# Gimbal-Mastboard.net
KiCad netlist of a schematic drawn in EAGLE
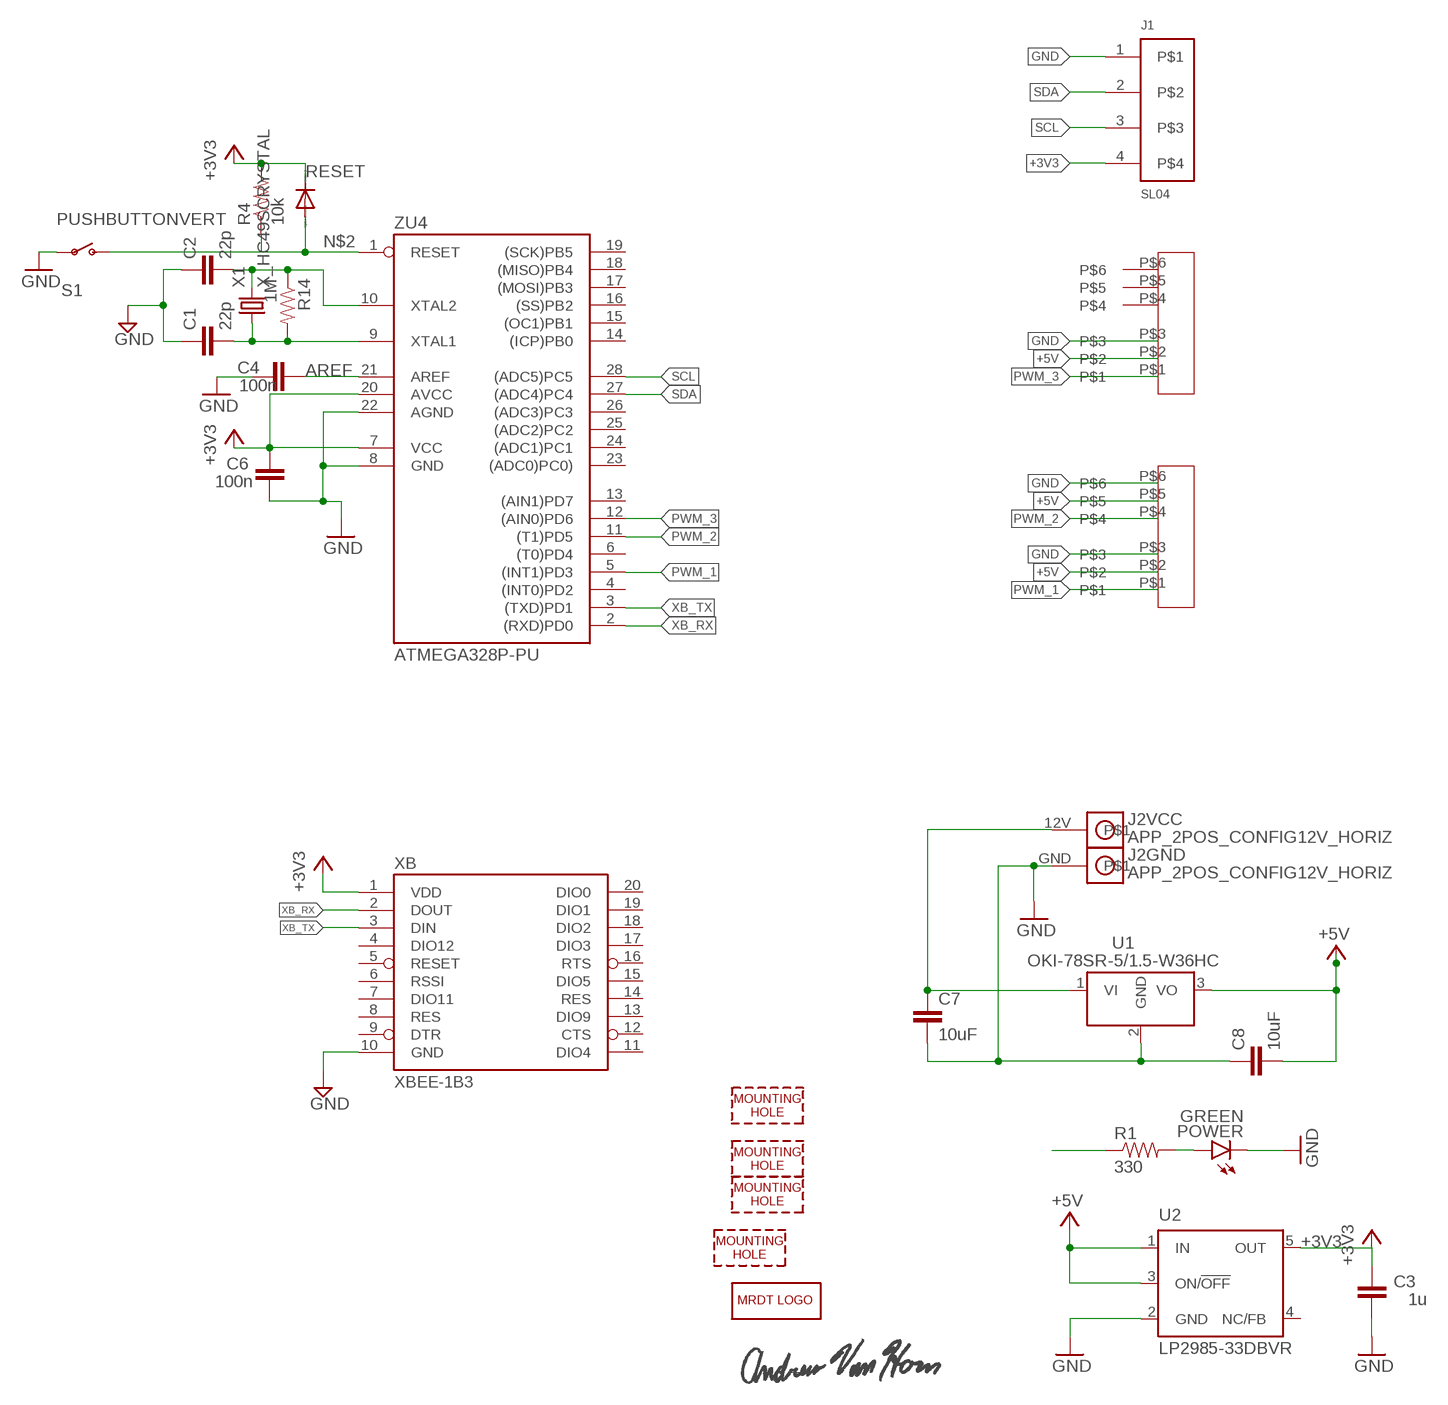
[diagram p0: schematic, sheet 1]

(export (version "E")
  (design (tool "Eeschema 10.0.6"))
  (components
    (comp (ref "C1")
      (value "22p")
      (footprint "eagle-import:0603-CAP")
      (libsource (lib "eagle-import") (part "SparkFun-Passives_CAP0603-CAP"))
    )
    (comp (ref "C2")
      (value "22p")
      (footprint "eagle-import:0603-CAP")
      (libsource (lib "eagle-import") (part "SparkFun-Passives_CAP0603-CAP"))
    )
    (comp (ref "C3")
      (value "1u")
      (footprint "eagle-import:C0603-ROUND")
      (libsource (lib "eagle-import") (part "C-EU0603-RND"))
    )
    (comp (ref "C4")
      (value "100n")
      (footprint "eagle-import:C0603-ROUND")
      (libsource (lib "eagle-import") (part "C-EU0603-RND"))
    )
    (comp (ref "C6")
      (value "100n")
      (footprint "eagle-import:C0603-ROUND")
      (libsource (lib "eagle-import") (part "C-EU0603-RND"))
    )
    (comp (ref "C7")
      (value "10uF")
      (footprint "eagle-import:0805")
      (libsource (lib "eagle-import") (part "CAP0805"))
    )
    (comp (ref "C8")
      (value "10uF")
      (footprint "eagle-import:0805")
      (libsource (lib "eagle-import") (part "CAP0805"))
    )
    (comp (ref "H1")
      (value "MOUNTING_HOLE#4")
      (footprint "eagle-import:#4_SCREW")
      (libsource (lib "eagle-import") (part "MOUNTING_HOLE#4"))
    )
    (comp (ref "H2")
      (value "MOUNTING_HOLE#4")
      (footprint "eagle-import:#4_SCREW")
      (libsource (lib "eagle-import") (part "MOUNTING_HOLE#4"))
    )
    (comp (ref "H3")
      (value "MOUNTING_HOLE#4")
      (footprint "eagle-import:#4_SCREW")
      (libsource (lib "eagle-import") (part "MOUNTING_HOLE#4"))
    )
    (comp (ref "H4")
      (value "MOUNTING_HOLE#4")
      (footprint "eagle-import:#4_SCREW")
      (libsource (lib "eagle-import") (part "MOUNTING_HOLE#4"))
    )
    (comp (ref "J1")
      (value "SL04")
      (footprint "eagle-import:MOLEX_SL_04_TH")
      (libsource (lib "eagle-import") (part "SL04"))
    )
    (comp (ref "J2")
      (value "APP_2POS_CONFIG12V_HORIZ")
      (footprint "eagle-import:APP45_12V_HORIZ_CONFIG")
      (libsource (lib "eagle-import") (part "APP_2POS_CONFIG12V_HORIZ"))
    )
    (comp (ref "LOGO1")
      (value "MRDT_LOGO")
      (footprint "eagle-import:MRDT_LOGO")
      (libsource (lib "eagle-import") (part "MRDT_LOGO"))
    )
    (comp (ref "POWER")
      (value "GREEN")
      (footprint "eagle-import:LED-1206")
      (libsource (lib "eagle-import") (part "LED-GREEN1206"))
    )
    (comp (ref "R1")
      (value "330")
      (footprint "eagle-import:0805")
      (libsource (lib "eagle-import") (part "0.22OHM-1/4W-1%(0805)"))
    )
    (comp (ref "R4")
      (value "10k")
      (footprint "eagle-import:0805")
      (libsource (lib "eagle-import") (part "0.22OHM-1/4W-1%(0805)"))
    )
    (comp (ref "R14")
      (value "1M")
      (footprint "eagle-import:0603-RES")
      (libsource (lib "eagle-import") (part "RESISTOR0603"))
    )
    (comp (ref "RESET")
      (value "CD1206-S01575")
      (footprint "eagle-import:MINIMELF")
      (libsource (lib "eagle-import") (part "DIODE-MINIMELF"))
    )
    (comp (ref "S1")
      (value "PUSHBUTTONVERT")
      (footprint "eagle-import:APEM-MJTP1243")
      (fields (field (name "PARTNO") "MJTP1243"))
      (libsource (lib "eagle-import") (part "PUSHBUTTONVERT"))
    )
    (comp (ref "U$1")
      (value "2X3_BOX_HEADER_FEMALE")
      (footprint "eagle-import:2X3_BOX_HEADER_FEMALE")
      (libsource (lib "eagle-import") (part "2X3_BOX_HEADER_FEMALE"))
    )
    (comp (ref "U$2")
      (value "2X3_BOX_HEADER_FEMALE")
      (footprint "eagle-import:2X3_BOX_HEADER_FEMALE")
      (libsource (lib "eagle-import") (part "2X3_BOX_HEADER_FEMALE"))
    )
    (comp (ref "U$3")
      (value "ANDREW_VAN_HORN_SIGNATURE")
      (footprint "eagle-import:ANDREW_VAN_HORN_SIGNATURE")
      (libsource (lib "eagle-import") (part "ANDREW_VAN_HORN_SIGNATURE"))
    )
    (comp (ref "U1")
      (value "OKI-78SR-5/1.5-W36HC")
      (footprint "eagle-import:OKI-78SR_HORIZ")
      (libsource (lib "eagle-import") (part "OKI-78SR-/1.5-W36?CH5"))
    )
    (comp (ref "U2")
      (value "LP2985-33DBVR")
      (footprint "eagle-import:SOT23-DBV")
      (libsource (lib "eagle-import") (part "LP2985-XXDBVR33"))
    )
    (comp (ref "X1")
      (value "X_HC49SCRYSTAL")
      (footprint "eagle-import:HC-49")
      (libsource (lib "eagle-import") (part "X_HC49SCRYSTAL"))
    )
    (comp (ref "XB")
      (value "XBEE-1B3")
      (footprint "eagle-import:XBEE-SMD")
      (libsource (lib "eagle-import") (part "XBEE-1B3"))
    )
    (comp (ref "ZU4")
      (value "ATMEGA328P-PU")
      (footprint "eagle-import:DIL28-3")
      (libsource (lib "eagle-import") (part "ATMEGA328P-PU"))
    )
  )
  (nets
    (net (code "1") (name "+3V3") (class "Default")
      (node (ref "C3") (pin "2") (pinfunction "2_2") (pintype "passive"))
      (node (ref "C6") (pin "2") (pinfunction "2_2") (pintype "passive"))
      (node (ref "J1") (pin "4") (pinfunction "P$4_4") (pintype "bidirectional"))
      (node (ref "R1") (pin "1") (pinfunction "1_1") (pintype "passive"))
      (node (ref "R4") (pin "2") (pinfunction "2_2") (pintype "passive"))
      (node (ref "RESET") (pin "C") (pinfunction "C_C") (pintype "passive"))
      (node (ref "U2") (pin "5") (pinfunction "OUT_5") (pintype "passive"))
      (node (ref "XB") (pin "1") (pinfunction "VDD_1") (pintype "power_in"))
      (node (ref "ZU4") (pin "20") (pinfunction "AVCC_20") (pintype "power_in"))
      (node (ref "ZU4") (pin "7") (pinfunction "VCC_7") (pintype "power_in"))
    )
    (net (code "2") (name "+5V") (class "Default")
      (node (ref "C8") (pin "2") (pinfunction "2_2") (pintype "passive"))
      (node (ref "U$1") (pin "P$2") (pinfunction "P$2_P$2") (pintype "bidirectional"))
      (node (ref "U$2") (pin "P$2") (pinfunction "P$2_P$2") (pintype "bidirectional"))
      (node (ref "U$2") (pin "P$5") (pinfunction "P$5_P$5") (pintype "bidirectional"))
      (node (ref "U1") (pin "3") (pinfunction "VO_3") (pintype "bidirectional"))
      (node (ref "U2") (pin "1") (pinfunction "IN_1") (pintype "input"))
      (node (ref "U2") (pin "3") (pinfunction "ON/~{OFF}_3") (pintype "input"))
    )
    (net (code "3") (name "/AREF") (class "Default")
      (node (ref "C4") (pin "2") (pinfunction "2_2") (pintype "passive"))
      (node (ref "ZU4") (pin "21") (pinfunction "AREF_21") (pintype "passive"))
    )
    (net (code "4") (name "/N$2") (class "Default")
      (node (ref "R4") (pin "1") (pinfunction "1_1") (pintype "passive"))
      (node (ref "RESET") (pin "A") (pinfunction "A_A") (pintype "passive"))
      (node (ref "S1") (pin "P$2") (pinfunction "S_P$2") (pintype "passive"))
      (node (ref "ZU4") (pin "1") (pinfunction "RESET_1") (pintype "input"))
    )
    (net (code "5") (name "GND") (class "Default")
      (node (ref "C1") (pin "1") (pinfunction "1_1") (pintype "passive"))
      (node (ref "C2") (pin "1") (pinfunction "1_1") (pintype "passive"))
      (node (ref "C3") (pin "1") (pinfunction "1_1") (pintype "passive"))
      (node (ref "C4") (pin "1") (pinfunction "1_1") (pintype "passive"))
      (node (ref "C6") (pin "1") (pinfunction "1_1") (pintype "passive"))
      (node (ref "C7") (pin "2") (pinfunction "2_2") (pintype "passive"))
      (node (ref "C8") (pin "1") (pinfunction "1_1") (pintype "passive"))
      (node (ref "J1") (pin "1") (pinfunction "P$1_1") (pintype "bidirectional"))
      (node (ref "J2") (pin "GND") (pinfunction "P$1_GND") (pintype "bidirectional"))
      (node (ref "POWER") (pin "C") (pinfunction "C_C") (pintype "passive"))
      (node (ref "S1") (pin "P$1") (pinfunction "P_P$1") (pintype "passive"))
      (node (ref "U$1") (pin "P$3") (pinfunction "P$3_P$3") (pintype "bidirectional"))
      (node (ref "U$2") (pin "P$3") (pinfunction "P$3_P$3") (pintype "bidirectional"))
      (node (ref "U$2") (pin "P$6") (pinfunction "P$6_P$6") (pintype "bidirectional"))
      (node (ref "U1") (pin "2") (pinfunction "GND_2") (pintype "bidirectional"))
      (node (ref "U2") (pin "2") (pinfunction "GND_2") (pintype "power_in"))
      (node (ref "XB") (pin "10") (pinfunction "GND_10") (pintype "power_in"))
      (node (ref "ZU4") (pin "22") (pinfunction "AGND_22") (pintype "power_in"))
      (node (ref "ZU4") (pin "8") (pinfunction "GND_8") (pintype "power_in"))
    )
    (net (code "6") (name "Net-(J2B-P$1)") (class "Default")
      (node (ref "C7") (pin "1") (pinfunction "1_1") (pintype "passive"))
      (node (ref "J2") (pin "12V") (pinfunction "P$1_12V") (pintype "bidirectional"))
      (node (ref "U1") (pin "1") (pinfunction "VI_1") (pintype "bidirectional"))
    )
    (net (code "7") (name "Net-(POWER-PadA)") (class "Default")
      (node (ref "POWER") (pin "A") (pinfunction "A_A") (pintype "passive"))
      (node (ref "R1") (pin "2") (pinfunction "2_2") (pintype "passive"))
    )
    (net (code "8") (name "Net-(X1-1)") (class "Default")
      (node (ref "C1") (pin "2") (pinfunction "2_2") (pintype "passive"))
      (node (ref "R14") (pin "2") (pinfunction "2_2") (pintype "passive"))
      (node (ref "X1") (pin "P$1") (pinfunction "1_P$1") (pintype "passive"))
      (node (ref "ZU4") (pin "9") (pinfunction "XTAL1_9") (pintype "bidirectional"))
    )
    (net (code "9") (name "Net-(X1-2)") (class "Default")
      (node (ref "C2") (pin "2") (pinfunction "2_2") (pintype "passive"))
      (node (ref "R14") (pin "1") (pinfunction "1_1") (pintype "passive"))
      (node (ref "X1") (pin "P$2") (pinfunction "2_P$2") (pintype "passive"))
      (node (ref "ZU4") (pin "10") (pinfunction "XTAL2_10") (pintype "bidirectional"))
    )
    (net (code "10") (name "PWM_1") (class "Default")
      (node (ref "U$2") (pin "P$1") (pinfunction "P$1_P$1") (pintype "bidirectional"))
      (node (ref "ZU4") (pin "5") (pinfunction "(INT1)PD3_5") (pintype "bidirectional"))
    )
    (net (code "11") (name "PWM_2") (class "Default")
      (node (ref "U$2") (pin "P$4") (pinfunction "P$4_P$4") (pintype "bidirectional"))
      (node (ref "ZU4") (pin "11") (pinfunction "(T1)PD5_11") (pintype "bidirectional"))
    )
    (net (code "12") (name "PWM_3") (class "Default")
      (node (ref "U$1") (pin "P$1") (pinfunction "P$1_P$1") (pintype "bidirectional"))
      (node (ref "ZU4") (pin "12") (pinfunction "(AIN0)PD6_12") (pintype "bidirectional"))
    )
    (net (code "13") (name "SCL") (class "Default")
      (node (ref "J1") (pin "3") (pinfunction "P$3_3") (pintype "bidirectional"))
      (node (ref "ZU4") (pin "28") (pinfunction "(ADC5)PC5_28") (pintype "bidirectional"))
    )
    (net (code "14") (name "SDA") (class "Default")
      (node (ref "J1") (pin "2") (pinfunction "P$2_2") (pintype "bidirectional"))
      (node (ref "ZU4") (pin "27") (pinfunction "(ADC4)PC4_27") (pintype "bidirectional"))
    )
    (net (code "15") (name "XB_RX") (class "Default")
      (node (ref "XB") (pin "2") (pinfunction "DOUT_2") (pintype "output"))
      (node (ref "ZU4") (pin "2") (pinfunction "(RXD)PD0_2") (pintype "bidirectional"))
    )
    (net (code "16") (name "XB_TX") (class "Default")
      (node (ref "XB") (pin "3") (pinfunction "DIN_3") (pintype "input"))
      (node (ref "ZU4") (pin "3") (pinfunction "(TXD)PD1_3") (pintype "bidirectional"))
    )
    (net (code "17") (name "unconnected-(U$1-PadP$4)") (class "Default")
      (node (ref "U$1") (pin "P$4") (pinfunction "P$4_P$4") (pintype "bidirectional"))
    )
    (net (code "18") (name "unconnected-(U$1-PadP$5)") (class "Default")
      (node (ref "U$1") (pin "P$5") (pinfunction "P$5_P$5") (pintype "bidirectional"))
    )
    (net (code "19") (name "unconnected-(U$1-PadP$6)") (class "Default")
      (node (ref "U$1") (pin "P$6") (pinfunction "P$6_P$6") (pintype "bidirectional"))
    )
    (net (code "20") (name "unconnected-(U2-NC{slash}FB-Pad4)") (class "Default")
      (node (ref "U2") (pin "4") (pinfunction "NC/FB_4") (pintype "passive"))
    )
    (net (code "21") (name "unconnected-(XB-CTS-Pad12)") (class "Default")
      (node (ref "XB") (pin "12") (pinfunction "CTS_12") (pintype "output"))
    )
    (net (code "22") (name "unconnected-(XB-DIO0-Pad20)") (class "Default")
      (node (ref "XB") (pin "20") (pinfunction "DIO0_20") (pintype "bidirectional"))
    )
    (net (code "23") (name "unconnected-(XB-DIO1-Pad19)") (class "Default")
      (node (ref "XB") (pin "19") (pinfunction "DIO1_19") (pintype "bidirectional"))
    )
    (net (code "24") (name "unconnected-(XB-DIO2-Pad18)") (class "Default")
      (node (ref "XB") (pin "18") (pinfunction "DIO2_18") (pintype "bidirectional"))
    )
    (net (code "25") (name "unconnected-(XB-DIO3-Pad17)") (class "Default")
      (node (ref "XB") (pin "17") (pinfunction "DIO3_17") (pintype "bidirectional"))
    )
    (net (code "26") (name "unconnected-(XB-DIO4-Pad11)") (class "Default")
      (node (ref "XB") (pin "11") (pinfunction "DIO4_11") (pintype "bidirectional"))
    )
    (net (code "27") (name "unconnected-(XB-DIO5-Pad15)") (class "Default")
      (node (ref "XB") (pin "15") (pinfunction "DIO5_15") (pintype "bidirectional"))
    )
    (net (code "28") (name "unconnected-(XB-DIO9-Pad13)") (class "Default")
      (node (ref "XB") (pin "13") (pinfunction "DIO9_13") (pintype "bidirectional"))
    )
    (net (code "29") (name "unconnected-(XB-DIO11-Pad7)") (class "Default")
      (node (ref "XB") (pin "7") (pinfunction "DIO11_7") (pintype "bidirectional"))
    )
    (net (code "30") (name "unconnected-(XB-DIO12-Pad4)") (class "Default")
      (node (ref "XB") (pin "4") (pinfunction "DIO12_4") (pintype "bidirectional"))
    )
    (net (code "31") (name "unconnected-(XB-DTR-Pad9)") (class "Default")
      (node (ref "XB") (pin "9") (pinfunction "DTR_9") (pintype "bidirectional"))
    )
    (net (code "32") (name "unconnected-(XB-RES-Pad8)") (class "Default")
      (node (ref "XB") (pin "8") (pinfunction "RES_8") (pintype "bidirectional"))
    )
    (net (code "33") (name "unconnected-(XB-RES-Pad14)") (class "Default")
      (node (ref "XB") (pin "14") (pinfunction "RES_14") (pintype "bidirectional"))
    )
    (net (code "34") (name "unconnected-(XB-RESET-Pad5)") (class "Default")
      (node (ref "XB") (pin "5") (pinfunction "RESET_5") (pintype "input"))
    )
    (net (code "35") (name "unconnected-(XB-RSSI-Pad6)") (class "Default")
      (node (ref "XB") (pin "6") (pinfunction "RSSI_6") (pintype "bidirectional"))
    )
    (net (code "36") (name "unconnected-(XB-RTS-Pad16)") (class "Default")
      (node (ref "XB") (pin "16") (pinfunction "RTS_16") (pintype "input"))
    )
    (net (code "37") (name "unconnected-(ZU4-(ADC0)PC0)-Pad23)") (class "Default")
      (node (ref "ZU4") (pin "23") (pinfunction "(ADC0)PC0)_23") (pintype "bidirectional"))
    )
    (net (code "38") (name "unconnected-(ZU4-(ADC1)PC1-Pad24)") (class "Default")
      (node (ref "ZU4") (pin "24") (pinfunction "(ADC1)PC1_24") (pintype "bidirectional"))
    )
    (net (code "39") (name "unconnected-(ZU4-(ADC2)PC2-Pad25)") (class "Default")
      (node (ref "ZU4") (pin "25") (pinfunction "(ADC2)PC2_25") (pintype "bidirectional"))
    )
    (net (code "40") (name "unconnected-(ZU4-(ADC3)PC3-Pad26)") (class "Default")
      (node (ref "ZU4") (pin "26") (pinfunction "(ADC3)PC3_26") (pintype "bidirectional"))
    )
    (net (code "41") (name "unconnected-(ZU4-(AIN1)PD7-Pad13)") (class "Default")
      (node (ref "ZU4") (pin "13") (pinfunction "(AIN1)PD7_13") (pintype "bidirectional"))
    )
    (net (code "42") (name "unconnected-(ZU4-(ICP)PB0-Pad14)") (class "Default")
      (node (ref "ZU4") (pin "14") (pinfunction "(ICP)PB0_14") (pintype "bidirectional"))
    )
    (net (code "43") (name "unconnected-(ZU4-(INT0)PD2-Pad4)") (class "Default")
      (node (ref "ZU4") (pin "4") (pinfunction "(INT0)PD2_4") (pintype "bidirectional"))
    )
    (net (code "44") (name "unconnected-(ZU4-(MISO)PB4-Pad18)") (class "Default")
      (node (ref "ZU4") (pin "18") (pinfunction "(MISO)PB4_18") (pintype "bidirectional"))
    )
    (net (code "45") (name "unconnected-(ZU4-(MOSI)PB3-Pad17)") (class "Default")
      (node (ref "ZU4") (pin "17") (pinfunction "(MOSI)PB3_17") (pintype "bidirectional"))
    )
    (net (code "46") (name "unconnected-(ZU4-(OC1)PB1-Pad15)") (class "Default")
      (node (ref "ZU4") (pin "15") (pinfunction "(OC1)PB1_15") (pintype "bidirectional"))
    )
    (net (code "47") (name "unconnected-(ZU4-(SCK)PB5-Pad19)") (class "Default")
      (node (ref "ZU4") (pin "19") (pinfunction "(SCK)PB5_19") (pintype "bidirectional"))
    )
    (net (code "48") (name "unconnected-(ZU4-(SS)PB2-Pad16)") (class "Default")
      (node (ref "ZU4") (pin "16") (pinfunction "(SS)PB2_16") (pintype "bidirectional"))
    )
    (net (code "49") (name "unconnected-(ZU4-(T0)PD4-Pad6)") (class "Default")
      (node (ref "ZU4") (pin "6") (pinfunction "(T0)PD4_6") (pintype "bidirectional"))
    )
  )
)
